# Atmega328PB.net
KiCad netlist of a schematic drawn in Altium Designer
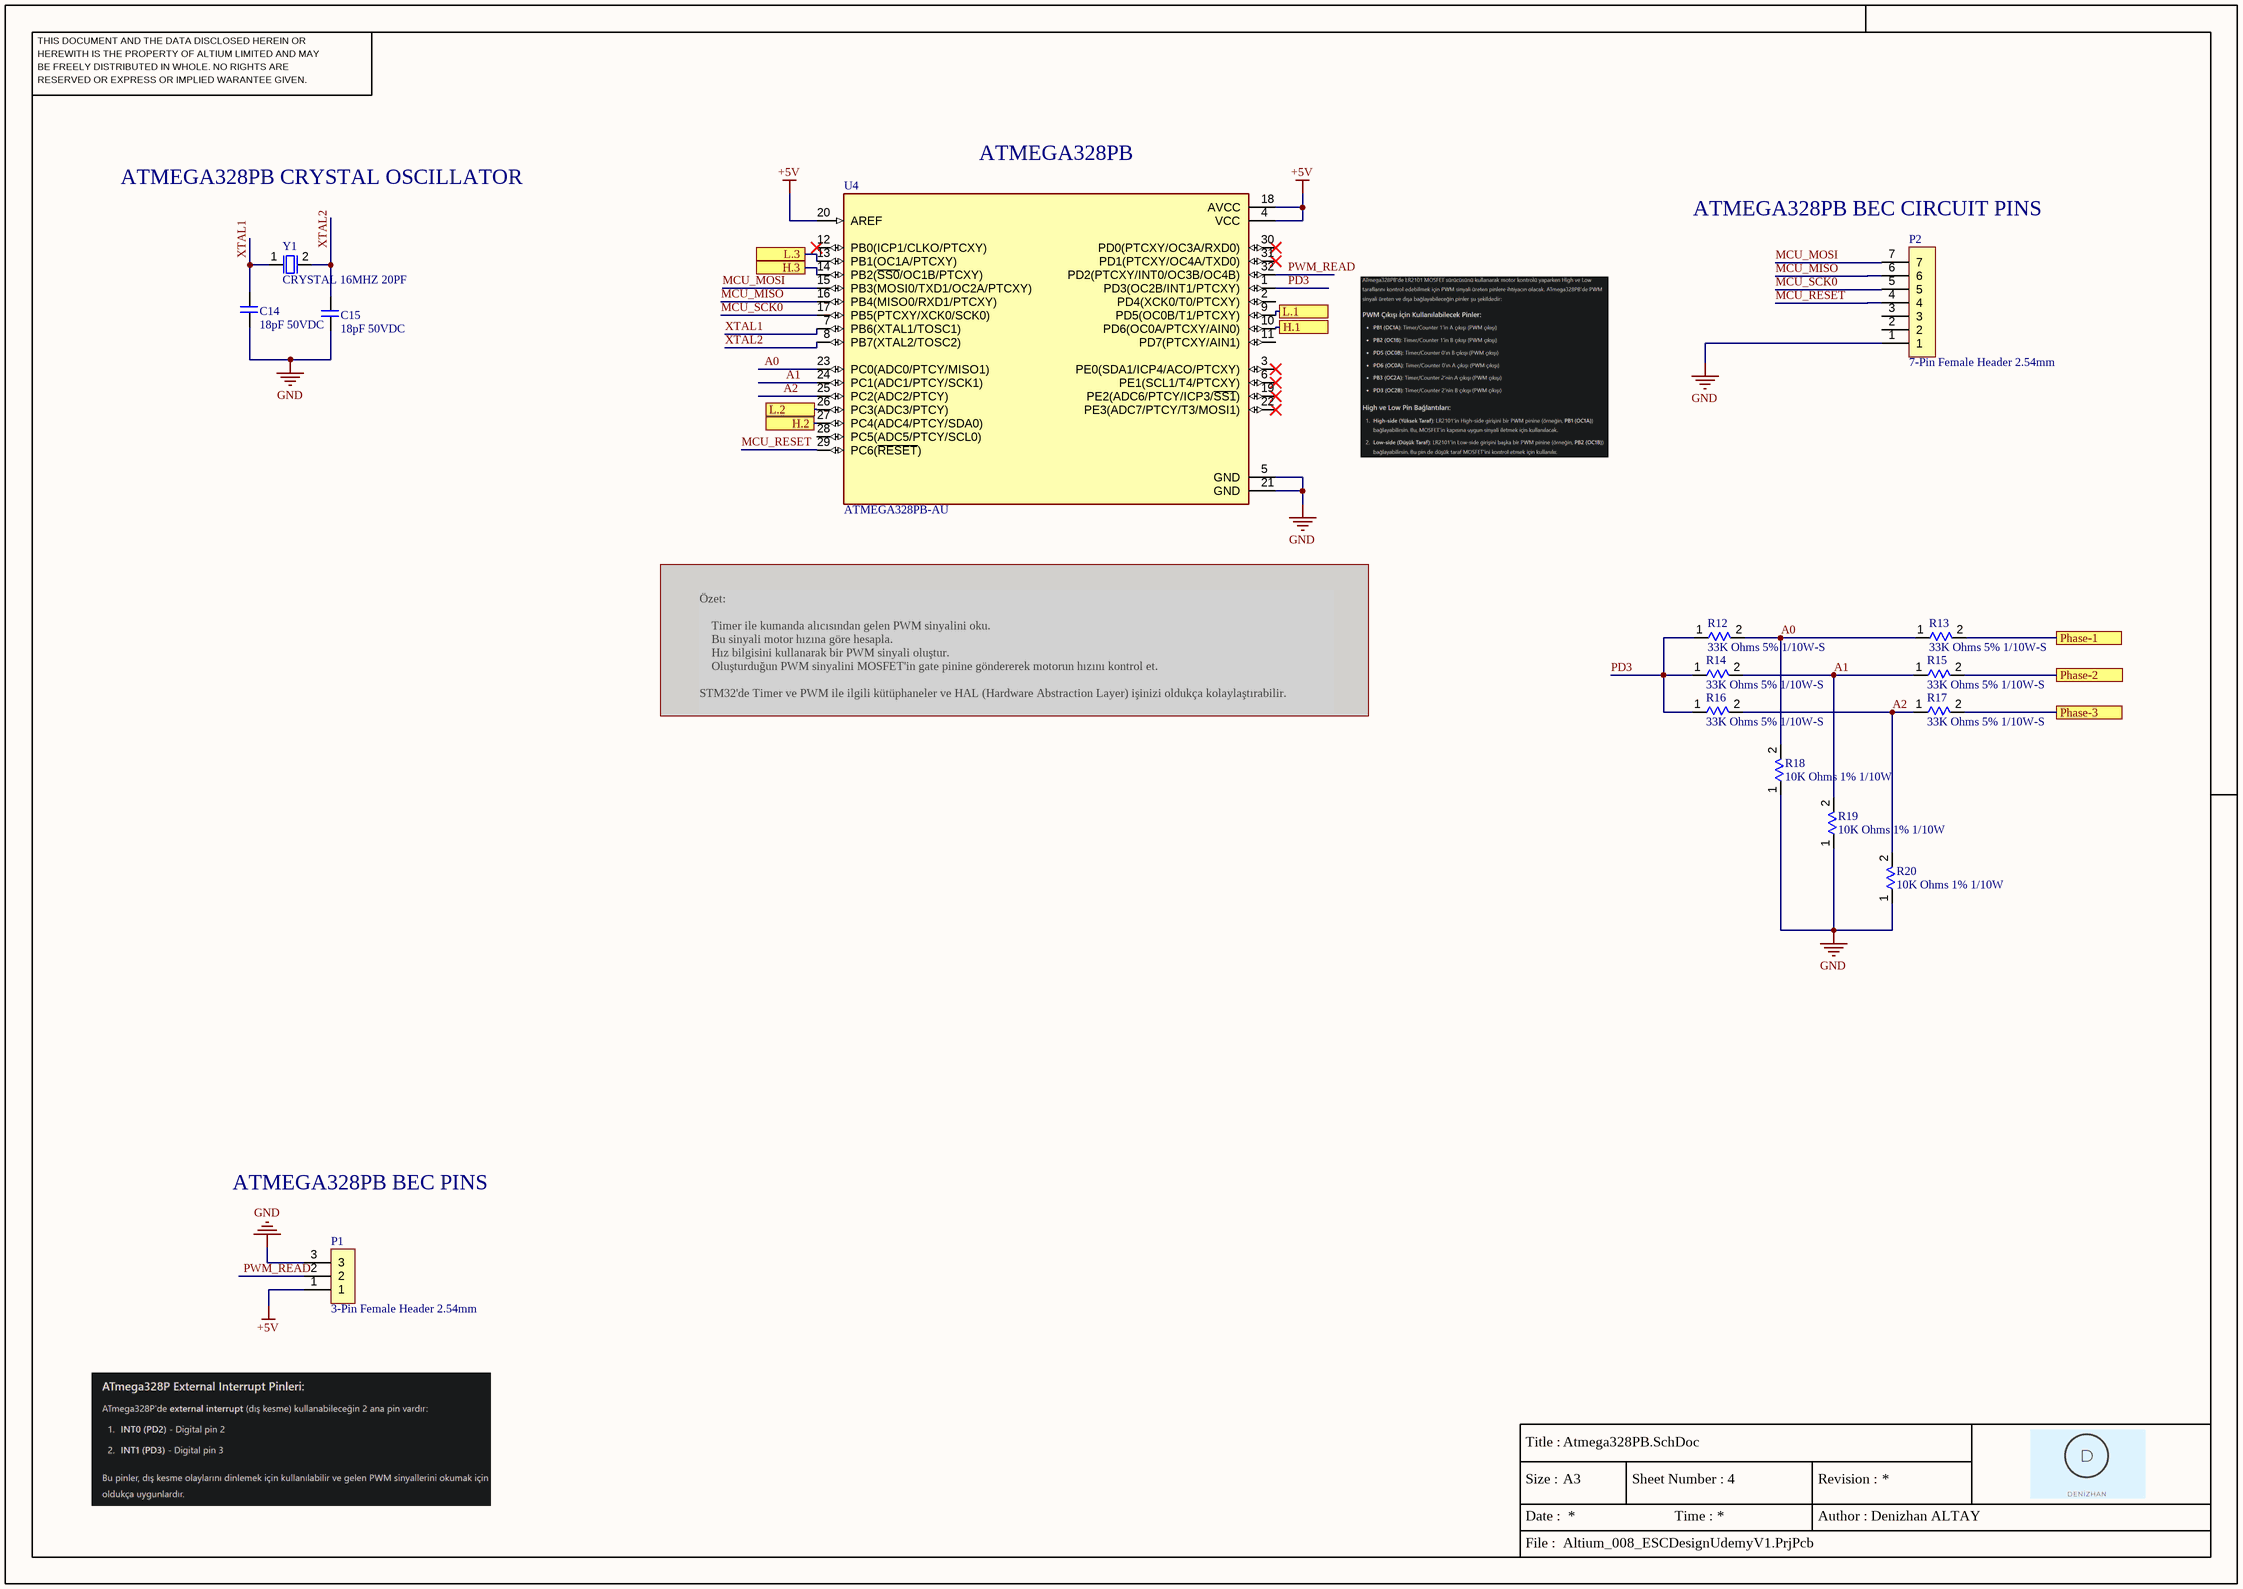
[diagram p0: Atmega328PB.SchDoc]

(export (version "E")
  (design (tool "Eeschema 10.0.6"))
  (components
    (comp (ref "C14")
      (value "18pF 50VDC")
      (footprint "0603_UNP_Cap")
      (description "MCF03JTN500180 - MLCC (1608) 0603 18pF 50VDC ±5% C0G (NP0)")
      (fields (field (name "MANUFACTURER") "VIKING") (field (name "PART NUMBER") "MCF03MTX250106"))
      (libsource (lib "GeneralDASchematicsLib") (part "MCF03JTN500180 - MLCC 0603 18pF 50VDC ±5% C0G (NP0)"))
    )
    (comp (ref "C15")
      (value "18pF 50VDC")
      (footprint "0603_UNP_Cap")
      (description "MCF03JTN500180 - MLCC (1608) 0603 18pF 50VDC ±5% C0G (NP0)")
      (fields (field (name "MANUFACTURER") "VIKING") (field (name "PART NUMBER") "MCF03MTX250106"))
      (libsource (lib "GeneralDASchematicsLib") (part "MCF03JTN500180 - MLCC 0603 18pF 50VDC ±5% C0G (NP0)"))
    )
    (comp (ref "P1")
      (value "3-Pin Female Header 2.54mm")
      (footprint "1x3 Pin Female Header 2.54mm")
      (libsource (lib "GeneralDASchematicsLib") (part "Single 3-Pin (2.54mm) Female Header"))
    )
    (comp (ref "P2")
      (value "7-Pin Female Header 2.54mm")
      (footprint "Single 7-Pin (2.54mm) Female Header")
      (libsource (lib "GeneralDASchematicsLib") (part "Single 7-Pin (2.54mm) Female Header"))
    )
    (comp (ref "R12")
      (value "33K Ohms 5% 1/10W-S")
      (footprint "0603_Resistor_Case")
      (description "0603SAJ0333T5E - RES.(1608) 0603 33K Ohms 5% 1/10W-S 100PPM")
      (fields (field (name "MANUFACTURER") "ROYALOHM") (field (name "PART NUMBER") "0603SAJ0333T5E"))
      (libsource (lib "GeneralDASchematicsLib") (part "0603SAJ0333T5E - RES. 0603 33K Ohms 5% 1/10W-S 100PPM"))
    )
    (comp (ref "R13")
      (value "33K Ohms 5% 1/10W-S")
      (footprint "0603_Resistor_Case")
      (description "0603SAJ0333T5E - RES.(1608) 0603 33K Ohms 5% 1/10W-S 100PPM")
      (fields (field (name "MANUFACTURER") "ROYALOHM") (field (name "PART NUMBER") "0603SAJ0333T5E"))
      (libsource (lib "GeneralDASchematicsLib") (part "0603SAJ0333T5E - RES. 0603 33K Ohms 5% 1/10W-S 100PPM"))
    )
    (comp (ref "R14")
      (value "33K Ohms 5% 1/10W-S")
      (footprint "0603_Resistor_Case")
      (description "0603SAJ0333T5E - RES.(1608) 0603 33K Ohms 5% 1/10W-S 100PPM")
      (fields (field (name "MANUFACTURER") "ROYALOHM") (field (name "PART NUMBER") "0603SAJ0333T5E"))
      (libsource (lib "GeneralDASchematicsLib") (part "0603SAJ0333T5E - RES. 0603 33K Ohms 5% 1/10W-S 100PPM"))
    )
    (comp (ref "R15")
      (value "33K Ohms 5% 1/10W-S")
      (footprint "0603_Resistor_Case")
      (description "0603SAJ0333T5E - RES.(1608) 0603 33K Ohms 5% 1/10W-S 100PPM")
      (fields (field (name "MANUFACTURER") "ROYALOHM") (field (name "PART NUMBER") "0603SAJ0333T5E"))
      (libsource (lib "GeneralDASchematicsLib") (part "0603SAJ0333T5E - RES. 0603 33K Ohms 5% 1/10W-S 100PPM"))
    )
    (comp (ref "R16")
      (value "33K Ohms 5% 1/10W-S")
      (footprint "0603_Resistor_Case")
      (description "0603SAJ0333T5E - RES.(1608) 0603 33K Ohms 5% 1/10W-S 100PPM")
      (fields (field (name "MANUFACTURER") "ROYALOHM") (field (name "PART NUMBER") "0603SAJ0333T5E"))
      (libsource (lib "GeneralDASchematicsLib") (part "0603SAJ0333T5E - RES. 0603 33K Ohms 5% 1/10W-S 100PPM"))
    )
    (comp (ref "R17")
      (value "33K Ohms 5% 1/10W-S")
      (footprint "0603_Resistor_Case")
      (description "0603SAJ0333T5E - RES.(1608) 0603 33K Ohms 5% 1/10W-S 100PPM")
      (fields (field (name "MANUFACTURER") "ROYALOHM") (field (name "PART NUMBER") "0603SAJ0333T5E"))
      (libsource (lib "GeneralDASchematicsLib") (part "0603SAJ0333T5E - RES. 0603 33K Ohms 5% 1/10W-S 100PPM"))
    )
    (comp (ref "R18")
      (value "10K Ohms 1% 1/10W")
      (footprint "0603_Resistor_Case")
      (description "RC0603FR-0710KL - 0603 10K Ohms 1% 1/10W 100PPM")
      (fields (field (name "MANUFACTURER") "HOTTECH") (field (name "PART NUMBER") "PS03W4F1003T5E"))
      (libsource (lib "GeneralDASchematicsLib") (part "RC0603FR-0710KL - 0603 10K Ohms 1% 1/10W 100PPM"))
    )
    (comp (ref "R19")
      (value "10K Ohms 1% 1/10W")
      (footprint "0603_Resistor_Case")
      (description "RC0603FR-0710KL - 0603 10K Ohms 1% 1/10W 100PPM")
      (fields (field (name "MANUFACTURER") "HOTTECH") (field (name "PART NUMBER") "PS03W4F1003T5E"))
      (libsource (lib "GeneralDASchematicsLib") (part "RC0603FR-0710KL - 0603 10K Ohms 1% 1/10W 100PPM"))
    )
    (comp (ref "R20")
      (value "10K Ohms 1% 1/10W")
      (footprint "0603_Resistor_Case")
      (description "RC0603FR-0710KL - 0603 10K Ohms 1% 1/10W 100PPM")
      (fields (field (name "MANUFACTURER") "HOTTECH") (field (name "PART NUMBER") "PS03W4F1003T5E"))
      (libsource (lib "GeneralDASchematicsLib") (part "RC0603FR-0710KL - 0603 10K Ohms 1% 1/10W 100PPM"))
    )
    (comp (ref "U4")
      (value "ATMEGA328PB-AU")
      (footprint "GeneralDASchematicsLibPcbLib:ATMEGA328PB-AU")
      (description "ATmega Series 20 MHz 32 KB Flash 2 KB SRAM 8-Bit Microcontroller - TQFP-32")
      (fields (field (name "MF") "{'manufacturer': u'Microchip Technology'}"))
      (libsource (lib "GeneralDASchematicsLib") (part "ATMEGA328PB-AU"))
    )
    (comp (ref "Y1")
      (value "CRYSTAL 16MHZ 20PF")
      (footprint "16MHZ_CrsytalOscillator")
      (description "AS-16.000-20-SMD-TR - CRYSTAL 16.0000MHZ 20PF SMD")
      (fields (field (name "PART NUMBER") "AS-16.000-20-SMD-TR"))
      (libsource (lib "GeneralDASchematicsLib") (part "AS-16.000-20-SMD-TR - CRYSTAL 16.0000MHZ 20PF SMD"))
    )
  )
  (nets
    (net (code "1") (name "+5V") (class "Default")
      (node (ref "P1") (pin "1") (pinfunction "1_1") (pintype "passive"))
      (node (ref "U4") (pin "18") (pinfunction "AVCC_18") (pintype "power_in"))
      (node (ref "U4") (pin "20") (pinfunction "AREF_20") (pintype "input"))
      (node (ref "U4") (pin "4") (pinfunction "VCC_4") (pintype "power_in"))
    )
    (net (code "2") (name "/A0") (class "Default")
      (node (ref "R12") (pin "2") (pintype "passive"))
      (node (ref "R13") (pin "1") (pintype "passive"))
      (node (ref "R18") (pin "2") (pintype "passive"))
      (node (ref "U4") (pin "23") (pinfunction "PC0(ADC0/PTCY/MISO1)_23") (pintype "bidirectional"))
    )
    (net (code "3") (name "/A1") (class "Default")
      (node (ref "R14") (pin "2") (pintype "passive"))
      (node (ref "R15") (pin "1") (pintype "passive"))
      (node (ref "R19") (pin "2") (pintype "passive"))
      (node (ref "U4") (pin "24") (pinfunction "PC1(ADC1/PTCY/SCK1)_24") (pintype "bidirectional"))
    )
    (net (code "4") (name "/A2") (class "Default")
      (node (ref "R16") (pin "2") (pintype "passive"))
      (node (ref "R17") (pin "1") (pintype "passive"))
      (node (ref "R20") (pin "2") (pintype "passive"))
      (node (ref "U4") (pin "25") (pinfunction "PC2(ADC2/PTCY)_25") (pintype "bidirectional"))
    )
    (net (code "5") (name "/H.1") (class "Default")
      (node (ref "U4") (pin "10") (pinfunction "PD6(OC0A/PTCXY/AIN0)_10") (pintype "bidirectional"))
    )
    (net (code "6") (name "/H.2") (class "Default")
      (node (ref "U4") (pin "27") (pinfunction "PC4(ADC4/PTCY/SDA0)_27") (pintype "bidirectional"))
    )
    (net (code "7") (name "/H.3") (class "Default")
      (node (ref "U4") (pin "14") (pinfunction "PB2(~{SS0}/OC1B/PTCXY)_14") (pintype "bidirectional"))
    )
    (net (code "8") (name "/L.1") (class "Default")
      (node (ref "U4") (pin "9") (pinfunction "PD5(OC0B/T1/PTCXY)_9") (pintype "bidirectional"))
    )
    (net (code "9") (name "/L.2") (class "Default")
      (node (ref "U4") (pin "26") (pinfunction "PC3(ADC3/PTCY)_26") (pintype "bidirectional"))
    )
    (net (code "10") (name "/L.3") (class "Default")
      (node (ref "U4") (pin "13") (pinfunction "PB1(OC1A/PTCXY)_13") (pintype "bidirectional"))
    )
    (net (code "11") (name "/MCU_MISO") (class "Default")
      (node (ref "P2") (pin "6") (pinfunction "6_6") (pintype "passive"))
      (node (ref "U4") (pin "16") (pinfunction "PB4(MISO0/RXD1/PTCXY)_16") (pintype "bidirectional"))
    )
    (net (code "12") (name "/MCU_MOSI") (class "Default")
      (node (ref "P2") (pin "7") (pinfunction "7_7") (pintype "passive"))
      (node (ref "U4") (pin "15") (pinfunction "PB3(MOSI0/TXD1/OC2A/PTCXY)_15") (pintype "bidirectional"))
    )
    (net (code "13") (name "/MCU_RESET") (class "Default")
      (node (ref "P2") (pin "4") (pinfunction "4_4") (pintype "passive"))
      (node (ref "U4") (pin "29") (pinfunction "PC6(~{RESET})_29") (pintype "bidirectional"))
    )
    (net (code "14") (name "/MCU_SCK0") (class "Default")
      (node (ref "P2") (pin "5") (pinfunction "5_5") (pintype "passive"))
      (node (ref "U4") (pin "17") (pinfunction "PB5(PTCXY/XCK0/SCK0)_17") (pintype "bidirectional"))
    )
    (net (code "15") (name "/PD3") (class "Default")
      (node (ref "R12") (pin "1") (pintype "passive"))
      (node (ref "R14") (pin "1") (pintype "passive"))
      (node (ref "R16") (pin "1") (pintype "passive"))
      (node (ref "U4") (pin "1") (pinfunction "PD3(OC2B/INT1/PTCXY)_1") (pintype "bidirectional"))
    )
    (net (code "16") (name "/PWM_READ") (class "Default")
      (node (ref "P1") (pin "2") (pinfunction "2_2") (pintype "passive"))
      (node (ref "U4") (pin "32") (pinfunction "PD2(PTCXY/INT0/OC3B/OC4B)_32") (pintype "bidirectional"))
    )
    (net (code "17") (name "/Phase-1") (class "Default") (node (ref "R13") (pin "2") (pintype "passive")))
    (net (code "18") (name "/Phase-2") (class "Default") (node (ref "R15") (pin "2") (pintype "passive")))
    (net (code "19") (name "/Phase-3") (class "Default") (node (ref "R17") (pin "2") (pintype "passive")))
    (net (code "20") (name "/XTAL1") (class "Default")
      (node (ref "C14") (pin "2") (pinfunction "2_2") (pintype "passive"))
      (node (ref "U4") (pin "7") (pinfunction "PB6(XTAL1/TOSC1)_7") (pintype "bidirectional"))
      (node (ref "Y1") (pin "1") (pintype "passive"))
    )
    (net (code "21") (name "/XTAL2") (class "Default")
      (node (ref "C15") (pin "2") (pinfunction "2_2") (pintype "passive"))
      (node (ref "U4") (pin "8") (pinfunction "PB7(XTAL2/TOSC2)_8") (pintype "bidirectional"))
      (node (ref "Y1") (pin "2") (pintype "passive"))
    )
    (net (code "22") (name "GND") (class "Default")
      (node (ref "C14") (pin "1") (pinfunction "1_1") (pintype "passive"))
      (node (ref "C15") (pin "1") (pinfunction "1_1") (pintype "passive"))
      (node (ref "P1") (pin "3") (pinfunction "3_3") (pintype "passive"))
      (node (ref "P2") (pin "1") (pinfunction "1_1") (pintype "passive"))
      (node (ref "R18") (pin "1") (pintype "passive"))
      (node (ref "R19") (pin "1") (pintype "passive"))
      (node (ref "R20") (pin "1") (pintype "passive"))
      (node (ref "U4") (pin "21") (pinfunction "GND_21") (pintype "power_in"))
      (node (ref "U4") (pin "5") (pinfunction "GND_5") (pintype "power_in"))
    )
    (net (code "23") (name "unconnected-(P2-Pad2)") (class "Default")
      (node (ref "P2") (pin "2") (pinfunction "2_2") (pintype "passive"))
    )
    (net (code "24") (name "unconnected-(P2-Pad3)") (class "Default")
      (node (ref "P2") (pin "3") (pinfunction "3_3") (pintype "passive"))
    )
    (net (code "25") (name "unconnected-(U4-PB0(ICP1{slash}CLKO{slash}PTCXY)-Pad12)") (class "Default")
      (node (ref "U4") (pin "12") (pinfunction "PB0(ICP1/CLKO/PTCXY)_12") (pintype "bidirectional+no_connect"))
    )
    (net (code "26") (name "unconnected-(U4-PC5(ADC5{slash}PTCY{slash}SCL0)-Pad28)") (class "Default")
      (node (ref "U4") (pin "28") (pinfunction "PC5(ADC5/PTCY/SCL0)_28") (pintype "bidirectional"))
    )
    (net (code "27") (name "unconnected-(U4-PD0(PTCXY{slash}OC3A{slash}RXD0)-Pad30)") (class "Default")
      (node (ref "U4") (pin "30") (pinfunction "PD0(PTCXY/OC3A/RXD0)_30") (pintype "bidirectional+no_connect"))
    )
    (net (code "28") (name "unconnected-(U4-PD1(PTCXY{slash}OC4A{slash}TXD0)-Pad31)") (class "Default")
      (node (ref "U4") (pin "31") (pinfunction "PD1(PTCXY/OC4A/TXD0)_31") (pintype "bidirectional+no_connect"))
    )
    (net (code "29") (name "unconnected-(U4-PD4(XCK0{slash}T0{slash}PTCXY)-Pad2)") (class "Default")
      (node (ref "U4") (pin "2") (pinfunction "PD4(XCK0/T0/PTCXY)_2") (pintype "bidirectional"))
    )
    (net (code "30") (name "unconnected-(U4-PD7(PTCXY{slash}AIN1)-Pad11)") (class "Default")
      (node (ref "U4") (pin "11") (pinfunction "PD7(PTCXY/AIN1)_11") (pintype "bidirectional"))
    )
    (net (code "31") (name "unconnected-(U4-PE0(SDA1{slash}ICP4{slash}ACO{slash}PTCXY)-Pad3)") (class "Default")
      (node (ref "U4") (pin "3") (pinfunction "PE0(SDA1/ICP4/ACO/PTCXY)_3") (pintype "bidirectional+no_connect"))
    )
    (net (code "32") (name "unconnected-(U4-PE1(SCL1{slash}T4{slash}PTCXY)-Pad6)") (class "Default")
      (node (ref "U4") (pin "6") (pinfunction "PE1(SCL1/T4/PTCXY)_6") (pintype "bidirectional+no_connect"))
    )
    (net (code "33") (name "unconnected-(U4-PE2(ADC6{slash}PTCY{slash}ICP3{slash}~{SS1})-Pad19)") (class "Default")
      (node (ref "U4") (pin "19") (pinfunction "PE2(ADC6/PTCY/ICP3/~{SS1})_19") (pintype "bidirectional+no_connect"))
    )
    (net (code "34") (name "unconnected-(U4-PE3(ADC7{slash}PTCY{slash}T3{slash}MOSI1)-Pad22)") (class "Default")
      (node (ref "U4") (pin "22") (pinfunction "PE3(ADC7/PTCY/T3/MOSI1)_22") (pintype "bidirectional+no_connect"))
    )
  )
)
